# powersource.net
KiCad netlist of a schematic drawn in EAGLE
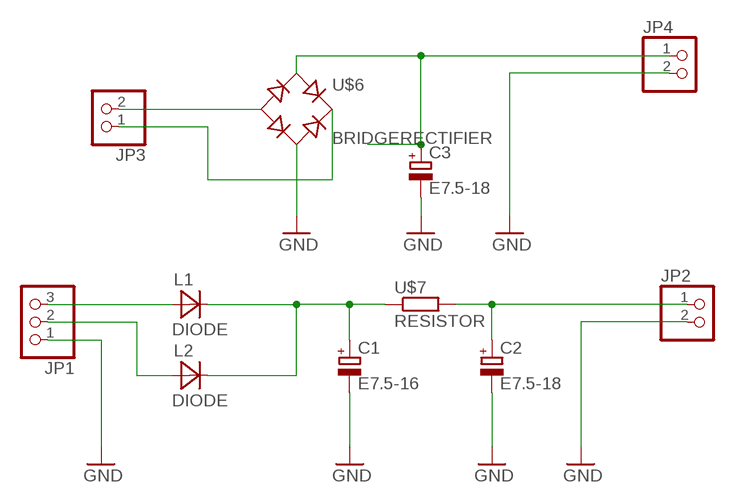
[diagram p0: schematic, sheet 1]

(export (version "E")
  (design (tool "Eeschema 10.0.6"))
  (components
    (comp (ref "C1")
      (value "E7.5-16")
      (footprint "eagle-import:E7,5-16")
      (libsource (lib "eagle-import") (part "E7.5-16"))
    )
    (comp (ref "C2")
      (value "E7.5-18")
      (footprint "eagle-import:E7,5-18")
      (libsource (lib "eagle-import") (part "E7.5-18"))
    )
    (comp (ref "C3")
      (value "E7.5-18")
      (footprint "eagle-import:E7,5-18")
      (libsource (lib "eagle-import") (part "E7.5-18"))
    )
    (comp (ref "JP1")
      (value "PINHD-1X3")
      (footprint "eagle-import:1X03")
      (libsource (lib "eagle-import") (part "PINHD-1X3"))
    )
    (comp (ref "JP2")
      (value "PINHD-1X2")
      (footprint "eagle-import:1X02")
      (libsource (lib "eagle-import") (part "PINHD-1X2"))
    )
    (comp (ref "JP3")
      (value "PINHD-1X2")
      (footprint "eagle-import:1X02")
      (libsource (lib "eagle-import") (part "PINHD-1X2"))
    )
    (comp (ref "JP4")
      (value "PINHD-1X2")
      (footprint "eagle-import:1X02")
      (libsource (lib "eagle-import") (part "PINHD-1X2"))
    )
    (comp (ref "L1")
      (value "DIODE")
      (footprint "eagle-import:DO07")
      (libsource (lib "eagle-import") (part "DIODE"))
    )
    (comp (ref "L2")
      (value "DIODE")
      (footprint "eagle-import:DO07")
      (libsource (lib "eagle-import") (part "DIODE"))
    )
    (comp (ref "U$6")
      (value "BRIDGERECTIFIER")
      (footprint "eagle-import:BRIDGERECTIFIER")
      (libsource (lib "eagle-import") (part "BRIDGERECTIFIER"))
    )
    (comp (ref "U$7")
      (value "RESISTOR")
      (footprint "eagle-import:RESISTOR")
      (libsource (lib "eagle-import") (part "RESISTOR"))
    )
  )
  (nets
    (net (code "1") (name "GND") (class "Default")
      (node (ref "C1") (pin "-") (pinfunction "-_-") (pintype "passive"))
      (node (ref "C2") (pin "-") (pinfunction "-_-") (pintype "passive"))
      (node (ref "C3") (pin "-") (pinfunction "-_-") (pintype "passive"))
      (node (ref "JP1") (pin "1") (pinfunction "1_1") (pintype "passive"))
      (node (ref "JP2") (pin "2") (pinfunction "2_2") (pintype "passive"))
      (node (ref "JP4") (pin "2") (pinfunction "2_2") (pintype "passive"))
      (node (ref "U$6") (pin "AC2") (pinfunction "AC2_AC2") (pintype "passive"))
    )
    (net (code "2") (name "Net-(C1-Pad+)") (class "Default")
      (node (ref "C1") (pin "+") (pinfunction "+_+") (pintype "passive"))
      (node (ref "L1") (pin "C") (pinfunction "C_C") (pintype "passive"))
      (node (ref "L2") (pin "C") (pinfunction "C_C") (pintype "passive"))
      (node (ref "U$7") (pin "1") (pinfunction "1_1") (pintype "passive"))
    )
    (net (code "3") (name "Net-(C2-Pad+)") (class "Default")
      (node (ref "C2") (pin "+") (pinfunction "+_+") (pintype "passive"))
      (node (ref "JP2") (pin "1") (pinfunction "1_1") (pintype "passive"))
      (node (ref "U$7") (pin "2") (pinfunction "2_2") (pintype "passive"))
    )
    (net (code "4") (name "Net-(C3-Pad+)") (class "Default")
      (node (ref "C3") (pin "+") (pinfunction "+_+") (pintype "passive"))
      (node (ref "JP4") (pin "1") (pinfunction "1_1") (pintype "passive"))
      (node (ref "U$6") (pin "AC1") (pinfunction "AC1_AC1") (pintype "passive"))
    )
    (net (code "5") (name "Net-(JP1-Pad2)") (class "Default")
      (node (ref "JP1") (pin "2") (pinfunction "2_2") (pintype "passive"))
      (node (ref "L2") (pin "A") (pinfunction "A_A") (pintype "passive"))
    )
    (net (code "6") (name "Net-(JP1-Pad3)") (class "Default")
      (node (ref "JP1") (pin "3") (pinfunction "3_3") (pintype "passive"))
      (node (ref "L1") (pin "A") (pinfunction "A_A") (pintype "passive"))
    )
    (net (code "7") (name "Net-(JP3-Pad1)") (class "Default")
      (node (ref "JP3") (pin "1") (pinfunction "1_1") (pintype "passive"))
      (node (ref "U$6") (pin "+") (pinfunction "+_+") (pintype "passive"))
    )
    (net (code "8") (name "Net-(JP3-Pad2)") (class "Default")
      (node (ref "JP3") (pin "2") (pinfunction "2_2") (pintype "passive"))
      (node (ref "U$6") (pin "-") (pinfunction "-_-") (pintype "passive"))
    )
  )
)
